# pixracer_sd_usb_can_i2c.net
KiCad netlist of a schematic drawn in Altium Designer
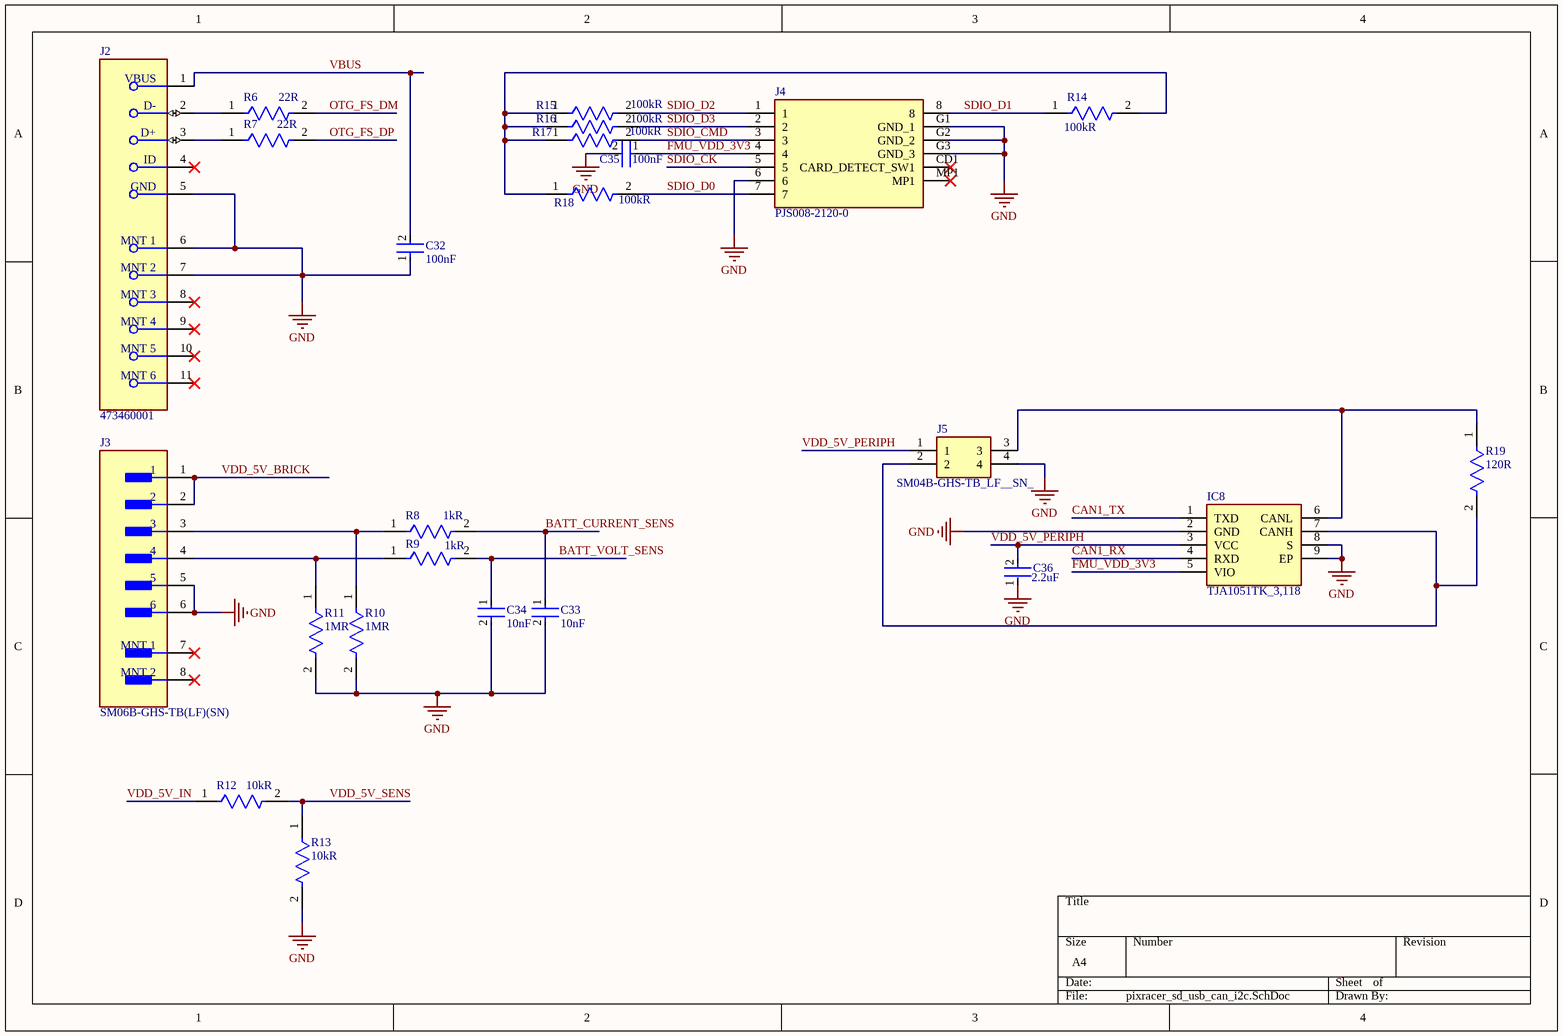
[diagram p0: pixracer_sd_usb_can_i2c.SchDoc]

(export (version "E")
  (design (tool "Eeschema 10.0.6"))
  (components
    (comp (ref "C32")
      (value "0603ZC104MAT2A")
      (footprint "FP-0603-L_1_6_0_15-W_0_81-IPC_B")
      (description "General Purpose Ceramic Capacitor, 0603, 100nF, 20%, X7R, 15%, 10V")
      (fields (field (name "TOLERANCE") "20%") (field (name "CAPACITANCE") "100nF"))
      (libsource (lib "Altium Content Vault") (part "02cd4be3c70576c341d710602a673aa"))
    )
    (comp (ref "C33")
      (value "C1608X5R1H103K080AA")
      (footprint "FP-C1608-080-0_1-MFG")
      (description "Multilayer Ceramic Capacitors 10nF ±10% 50V X5R SMD 0603")
      (fields (field (name "TOLERANCE") "10%") (field (name "CAPACITANCE") "10nF"))
      (libsource (lib "Altium Content Vault") (part "236180d848d6139a670b325ea6854c9"))
    )
    (comp (ref "C34")
      (value "C1608X5R1H103K080AA")
      (footprint "FP-C1608-080-0_1-MFG")
      (description "Multilayer Ceramic Capacitors 10nF ±10% 50V X5R SMD 0603")
      (fields (field (name "TOLERANCE") "10%") (field (name "CAPACITANCE") "10nF"))
      (libsource (lib "Altium Content Vault") (part "236180d848d6139a670b325ea6854c9"))
    )
    (comp (ref "C35")
      (value "0603ZC104MAT2A")
      (footprint "FP-0603-L_1_6_0_15-W_0_81-IPC_B")
      (description "General Purpose Ceramic Capacitor, 0603, 100nF, 20%, X7R, 15%, 10V")
      (fields (field (name "TOLERANCE") "20%") (field (name "CAPACITANCE") "100nF"))
      (libsource (lib "Altium Content Vault") (part "02cd4be3c70576c341d710602a673aa"))
    )
    (comp (ref "C36")
      (value "C1608X7R1A225K080AC")
      (footprint "FP-C1608-080-0_1-MFG")
      (description "Multilayer Ceramic Capacitors 2.2μF ±10% 10V X7R SMD 0603")
      (fields (field (name "CAPACITANCE") "2.2uF") (field (name "TOLERANCE") "10%"))
      (libsource (lib "Altium Content Vault") (part "236180d848d6139a670b325ea6854c9"))
    )
    (comp (ref "IC8")
      (value "TJA1051TK_3,118")
      (footprint "SamacSys:SON65P300X300X100-9N-D")
      (description "Integrated Circuit")
      (fields
        (field (name "MANUFACTURER_PART_NUMBER") "TJA1051TK/3,118")
        (field (name "MOUSER PART NUMBER") "771-TJA1051TK/3118")
      )
      (libsource (lib "*") (part "TJA1051TK_3,118"))
    )
    (comp (ref "J2")
      (value "473460001")
      (footprint "FP-473460001-MFG")
      (description "CONN RCPT USB2.0 MICRO B SMD R/A")
      (fields
        (field (name "OCTOPART") "https://octopart.com/47346-0001-molex-7164928")
        (field (name "MANUFACTURER") "Molex")
      )
      (libsource (lib "Altium Content Vault") (part "53ae1f1d9b557310b43ca686e5bb76a"))
    )
    (comp (ref "J3")
      (value "SM06B-GHS-TB(LF)(SN)")
      (footprint "FP-SM06B-GHS-TB_LF_SN-MFG")
      (description "CONN HEADER SMD R/A 6POS 1.25MM")
      (libsource (lib "Altium Content Vault") (part "ed24c53d9ba001d1a2a686240a95171"))
    )
    (comp (ref "J4")
      (value "PJS008-2120-0")
      (footprint "SamacSys:PJS00821200")
      (description "Connector")
      (fields (field (name "MOUSER PART NUMBER") "945-PJS008-2120-0"))
      (libsource (lib "*") (part "PJS008-2120-0"))
    )
    (comp (ref "J5")
      (value "SM04B-GHS-TB_LF__SN_")
      (footprint "SamacSys:SM04B-GHS-TB")
      (description "Connector")
      (fields (field (name "MANUFACTURER_PART_NUMBER") "SM04B-GHS-TB(LF)(SN)"))
      (libsource (lib "*") (part "SM04B-GHS-TB_LF__SN_"))
    )
    (comp (ref "R6")
      (value "CRCW060322R0JNEAHP")
      (footprint "FP-CRCW0603-HPe3-IPC_A")
      (description "RES Thick Film, 22Ω, 5%, 0.33W, 200ppm/°C, 0603")
      (fields (field (name "TOLERANCE") "5%") (field (name "RESISTANCE") "22R"))
      (libsource (lib "Altium Content Vault") (part "1029c3af85768c4190bb7ad29bc67b5"))
    )
    (comp (ref "R7")
      (value "CRCW060322R0JNEAHP")
      (footprint "FP-CRCW0603-HPe3-IPC_A")
      (description "RES Thick Film, 22Ω, 5%, 0.33W, 200ppm/°C, 0603")
      (fields (field (name "TOLERANCE") "5%") (field (name "RESISTANCE") "22R"))
      (libsource (lib "Altium Content Vault") (part "1029c3af85768c4190bb7ad29bc67b5"))
    )
    (comp (ref "R8")
      (value "RC1608J102CS")
      (footprint "FP-RC1608-IPC_A")
      (description "Res Thick Film 0603 1kΩ 5% 0.1W ±100ppm/°C Molded SMD T/R")
      (fields (field (name "RESISTANCE") "1kR") (field (name "TOLERANCE") "5%"))
      (libsource (lib "Altium Content Vault") (part "1029c3af85768c4190bb7ad29bc67b5"))
    )
    (comp (ref "R9")
      (value "RC1608J102CS")
      (footprint "FP-RC1608-IPC_A")
      (description "Res Thick Film 0603 1kΩ 5% 0.1W ±100ppm/°C Molded SMD T/R")
      (fields (field (name "RESISTANCE") "1kR") (field (name "TOLERANCE") "5%"))
      (libsource (lib "Altium Content Vault") (part "1029c3af85768c4190bb7ad29bc67b5"))
    )
    (comp (ref "R10")
      (value "CRCW06031M00JNEAHP")
      (footprint "FP-CRCW0603-HPe3-IPC_A")
      (description "RES Thick Film, 1MΩ, 5%, 0.33W, 200ppm/°C, 0603")
      (fields (field (name "TOLERANCE") "5%") (field (name "RESISTANCE") "1MR"))
      (libsource (lib "Altium Content Vault") (part "1029c3af85768c4190bb7ad29bc67b5"))
    )
    (comp (ref "R11")
      (value "CRCW06031M00JNEAHP")
      (footprint "FP-CRCW0603-HPe3-IPC_A")
      (description "RES Thick Film, 1MΩ, 5%, 0.33W, 200ppm/°C, 0603")
      (fields (field (name "TOLERANCE") "5%") (field (name "RESISTANCE") "1MR"))
      (libsource (lib "Altium Content Vault") (part "1029c3af85768c4190bb7ad29bc67b5"))
    )
    (comp (ref "R12")
      (value "ERJ-3GEYJ103V")
      (footprint "FP-ERJ3G-IPC_C")
      (description "RES SMD 10K OHM 5% 1/10W 0603")
      (fields (field (name "TOLERANCE") "5%") (field (name "RESISTANCE") "10kR"))
      (libsource (lib "Altium Content Vault") (part "1029c3af85768c4190bb7ad29bc67b5"))
    )
    (comp (ref "R13")
      (value "ERJ-3GEYJ103V")
      (footprint "FP-ERJ3G-IPC_C")
      (description "RES SMD 10K OHM 5% 1/10W 0603")
      (fields (field (name "TOLERANCE") "5%") (field (name "RESISTANCE") "10kR"))
      (libsource (lib "Altium Content Vault") (part "1029c3af85768c4190bb7ad29bc67b5"))
    )
    (comp (ref "R14")
      (value "RMCF0603JT100K")
      (footprint "FP-RMCF0603-IPC_C")
      (description "100kΩ ±5% 0.1W 0603 Thick Film Chip Resistor AEC-Q200 compliant")
      (fields (field (name "RESISTANCE") "100kR") (field (name "TOLERANCE") "5%"))
      (libsource (lib "Altium Content Vault") (part "1029c3af85768c4190bb7ad29bc67b5"))
    )
    (comp (ref "R15")
      (value "RMCF0603JT100K")
      (footprint "FP-RMCF0603-IPC_C")
      (description "100kΩ ±5% 0.1W 0603 Thick Film Chip Resistor AEC-Q200 compliant")
      (fields (field (name "RESISTANCE") "100kR") (field (name "TOLERANCE") "5%"))
      (libsource (lib "Altium Content Vault") (part "1029c3af85768c4190bb7ad29bc67b5"))
    )
    (comp (ref "R16")
      (value "RMCF0603JT100K")
      (footprint "FP-RMCF0603-IPC_C")
      (description "100kΩ ±5% 0.1W 0603 Thick Film Chip Resistor AEC-Q200 compliant")
      (fields (field (name "RESISTANCE") "100kR") (field (name "TOLERANCE") "5%"))
      (libsource (lib "Altium Content Vault") (part "1029c3af85768c4190bb7ad29bc67b5"))
    )
    (comp (ref "R17")
      (value "RMCF0603JT100K")
      (footprint "FP-RMCF0603-IPC_C")
      (description "100kΩ ±5% 0.1W 0603 Thick Film Chip Resistor AEC-Q200 compliant")
      (fields (field (name "RESISTANCE") "100kR") (field (name "TOLERANCE") "5%"))
      (libsource (lib "Altium Content Vault") (part "1029c3af85768c4190bb7ad29bc67b5"))
    )
    (comp (ref "R18")
      (value "RMCF0603JT100K")
      (footprint "FP-RMCF0603-IPC_C")
      (description "100kΩ ±5% 0.1W 0603 Thick Film Chip Resistor AEC-Q200 compliant")
      (fields (field (name "RESISTANCE") "100kR") (field (name "TOLERANCE") "5%"))
      (libsource (lib "Altium Content Vault") (part "1029c3af85768c4190bb7ad29bc67b5"))
    )
    (comp (ref "R19")
      (value "MCT06030D1200BP100")
      (footprint "FP-MCT0603-MFG")
      (description "RES SMD 100 OHM 1% 1/8W 0603")
      (fields (field (name "RESISTANCE") "120R") (field (name "TOLERANCE") "0.1%"))
      (libsource (lib "Altium Content Vault") (part "1029c3af85768c4190bb7ad29bc67b5"))
    )
  )
  (nets
    (net (code "1") (name "/BATT_CURRENT_SENS") (class "Default")
      (node (ref "C33") (pin "1") (pinfunction "1_1") (pintype "passive"))
      (node (ref "R8") (pin "2") (pinfunction "2_2") (pintype "passive"))
    )
    (net (code "2") (name "/BATT_VOLT_SENS") (class "Default")
      (node (ref "C34") (pin "1") (pinfunction "1_1") (pintype "passive"))
      (node (ref "R9") (pin "2") (pinfunction "2_2") (pintype "passive"))
    )
    (net (code "3") (name "/CAN1_RX") (class "Default")
      (node (ref "IC8") (pin "4") (pinfunction "RXD_4") (pintype "passive"))
    )
    (net (code "4") (name "/CAN1_TX") (class "Default")
      (node (ref "IC8") (pin "1") (pinfunction "TXD_1") (pintype "passive"))
    )
    (net (code "5") (name "/FMU_VDD_3V3") (class "Default")
      (node (ref "C35") (pin "1") (pinfunction "1_1") (pintype "passive"))
      (node (ref "IC8") (pin "5") (pinfunction "VIO_5") (pintype "passive"))
      (node (ref "J4") (pin "4") (pinfunction "4_4") (pintype "passive"))
    )
    (net (code "6") (name "/OTG_FS_DM") (class "Default")
      (node (ref "R6") (pin "2") (pinfunction "2_2") (pintype "passive"))
    )
    (net (code "7") (name "/OTG_FS_DP") (class "Default")
      (node (ref "R7") (pin "2") (pinfunction "2_2") (pintype "passive"))
    )
    (net (code "8") (name "/SDIO_CK") (class "Default")
      (node (ref "J4") (pin "5") (pinfunction "5_5") (pintype "passive"))
    )
    (net (code "9") (name "/SDIO_CMD") (class "Default")
      (node (ref "J4") (pin "3") (pinfunction "3_3") (pintype "passive"))
      (node (ref "R17") (pin "2") (pinfunction "2_2") (pintype "passive"))
    )
    (net (code "10") (name "/SDIO_D0") (class "Default")
      (node (ref "J4") (pin "7") (pinfunction "7_7") (pintype "passive"))
      (node (ref "R18") (pin "2") (pinfunction "2_2") (pintype "passive"))
    )
    (net (code "11") (name "/SDIO_D1") (class "Default")
      (node (ref "J4") (pin "8") (pinfunction "8_8") (pintype "passive"))
      (node (ref "R14") (pin "1") (pinfunction "1_1") (pintype "passive"))
    )
    (net (code "12") (name "/SDIO_D2") (class "Default")
      (node (ref "J4") (pin "1") (pinfunction "1_1") (pintype "passive"))
      (node (ref "R15") (pin "2") (pinfunction "2_2") (pintype "passive"))
    )
    (net (code "13") (name "/SDIO_D3") (class "Default")
      (node (ref "J4") (pin "2") (pinfunction "2_2") (pintype "passive"))
      (node (ref "R16") (pin "2") (pinfunction "2_2") (pintype "passive"))
    )
    (net (code "14") (name "/VBUS") (class "Default")
      (node (ref "C32") (pin "2") (pinfunction "2_2") (pintype "passive"))
      (node (ref "J2") (pin "1") (pinfunction "VBUS_1") (pintype "power_in"))
    )
    (net (code "15") (name "/VDD_5V_BRICK") (class "Default")
      (node (ref "J3") (pin "1") (pinfunction "1_1") (pintype "passive"))
      (node (ref "J3") (pin "2") (pinfunction "2_2") (pintype "passive"))
    )
    (net (code "16") (name "/VDD_5V_IN") (class "Default")
      (node (ref "R12") (pin "1") (pinfunction "1_1") (pintype "passive"))
    )
    (net (code "17") (name "/VDD_5V_PERIPH") (class "Default")
      (node (ref "C36") (pin "2") (pinfunction "2_2") (pintype "passive"))
      (node (ref "IC8") (pin "3") (pinfunction "VCC_3") (pintype "passive"))
      (node (ref "J5") (pin "1") (pinfunction "1_1") (pintype "passive"))
    )
    (net (code "18") (name "/VDD_5V_SENS") (class "Default")
      (node (ref "R12") (pin "2") (pinfunction "2_2") (pintype "passive"))
      (node (ref "R13") (pin "1") (pinfunction "1_1") (pintype "passive"))
    )
    (net (code "19") (name "GND") (class "Default")
      (node (ref "C32") (pin "1") (pinfunction "1_1") (pintype "passive"))
      (node (ref "C33") (pin "2") (pinfunction "2_2") (pintype "passive"))
      (node (ref "C34") (pin "2") (pinfunction "2_2") (pintype "passive"))
      (node (ref "C35") (pin "2") (pinfunction "2_2") (pintype "passive"))
      (node (ref "C36") (pin "1") (pinfunction "1_1") (pintype "passive"))
      (node (ref "IC8") (pin "2") (pinfunction "GND_2") (pintype "passive"))
      (node (ref "IC8") (pin "8") (pinfunction "S_8") (pintype "passive"))
      (node (ref "IC8") (pin "9") (pinfunction "EP_9") (pintype "passive"))
      (node (ref "J2") (pin "5") (pinfunction "GND_5") (pintype "power_in"))
      (node (ref "J2") (pin "6") (pinfunction "MNT_1_6") (pintype "passive"))
      (node (ref "J2") (pin "7") (pinfunction "MNT_2_7") (pintype "passive"))
      (node (ref "J3") (pin "5") (pinfunction "5_5") (pintype "passive"))
      (node (ref "J3") (pin "6") (pinfunction "6_6") (pintype "passive"))
      (node (ref "J4") (pin "6") (pinfunction "6_6") (pintype "passive"))
      (node (ref "J4") (pin "G1") (pinfunction "GND_1_G1") (pintype "passive"))
      (node (ref "J4") (pin "G2") (pinfunction "GND_2_G2") (pintype "passive"))
      (node (ref "J4") (pin "G3") (pinfunction "GND_3_G3") (pintype "passive"))
      (node (ref "J5") (pin "4") (pinfunction "4_4") (pintype "passive"))
      (node (ref "R10") (pin "2") (pinfunction "2_2") (pintype "passive"))
      (node (ref "R11") (pin "2") (pinfunction "2_2") (pintype "passive"))
      (node (ref "R13") (pin "2") (pinfunction "2_2") (pintype "passive"))
    )
    (net (code "20") (name "Net-(IC8-CANH)") (class "Default")
      (node (ref "IC8") (pin "7") (pinfunction "CANH_7") (pintype "passive"))
      (node (ref "J5") (pin "2") (pinfunction "2_2") (pintype "passive"))
      (node (ref "R19") (pin "2") (pinfunction "2_2") (pintype "passive"))
    )
    (net (code "21") (name "Net-(IC8-CANL)") (class "Default")
      (node (ref "IC8") (pin "6") (pinfunction "CANL_6") (pintype "passive"))
      (node (ref "J5") (pin "3") (pinfunction "3_3") (pintype "passive"))
      (node (ref "R19") (pin "1") (pinfunction "1_1") (pintype "passive"))
    )
    (net (code "22") (name "Net-(J2-D+)") (class "Default")
      (node (ref "J2") (pin "3") (pinfunction "D+_3") (pintype "bidirectional"))
      (node (ref "R7") (pin "1") (pinfunction "1_1") (pintype "passive"))
    )
    (net (code "23") (name "Net-(J2-D-)") (class "Default")
      (node (ref "J2") (pin "2") (pinfunction "D-_2") (pintype "bidirectional"))
      (node (ref "R6") (pin "1") (pinfunction "1_1") (pintype "passive"))
    )
    (net (code "24") (name "Net-(J3-Pad3)") (class "Default")
      (node (ref "J3") (pin "3") (pinfunction "3_3") (pintype "passive"))
      (node (ref "R10") (pin "1") (pinfunction "1_1") (pintype "passive"))
      (node (ref "R8") (pin "1") (pinfunction "1_1") (pintype "passive"))
    )
    (net (code "25") (name "Net-(J3-Pad4)") (class "Default")
      (node (ref "J3") (pin "4") (pinfunction "4_4") (pintype "passive"))
      (node (ref "R11") (pin "1") (pinfunction "1_1") (pintype "passive"))
      (node (ref "R9") (pin "1") (pinfunction "1_1") (pintype "passive"))
    )
    (net (code "26") (name "Net-(R14-Pad2)") (class "Default")
      (node (ref "R14") (pin "2") (pinfunction "2_2") (pintype "passive"))
      (node (ref "R15") (pin "1") (pinfunction "1_1") (pintype "passive"))
      (node (ref "R16") (pin "1") (pinfunction "1_1") (pintype "passive"))
      (node (ref "R17") (pin "1") (pinfunction "1_1") (pintype "passive"))
      (node (ref "R18") (pin "1") (pinfunction "1_1") (pintype "passive"))
    )
    (net (code "27") (name "unconnected-(J2-ID-Pad4)") (class "Default")
      (node (ref "J2") (pin "4") (pinfunction "ID_4") (pintype "passive+no_connect"))
    )
    (net (code "28") (name "unconnected-(J2-MNT_3-Pad8)") (class "Default")
      (node (ref "J2") (pin "8") (pinfunction "MNT_3_8") (pintype "passive+no_connect"))
    )
    (net (code "29") (name "unconnected-(J2-MNT_4-Pad9)") (class "Default")
      (node (ref "J2") (pin "9") (pinfunction "MNT_4_9") (pintype "passive+no_connect"))
    )
    (net (code "30") (name "unconnected-(J2-MNT_5-Pad10)") (class "Default")
      (node (ref "J2") (pin "10") (pinfunction "MNT_5_10") (pintype "passive+no_connect"))
    )
    (net (code "31") (name "unconnected-(J2-MNT_6-Pad11)") (class "Default")
      (node (ref "J2") (pin "11") (pinfunction "MNT_6_11") (pintype "passive+no_connect"))
    )
    (net (code "32") (name "unconnected-(J3-MNT_1-Pad7)") (class "Default")
      (node (ref "J3") (pin "7") (pinfunction "MNT_1_7") (pintype "passive+no_connect"))
    )
    (net (code "33") (name "unconnected-(J3-MNT_2-Pad8)") (class "Default")
      (node (ref "J3") (pin "8") (pinfunction "MNT_2_8") (pintype "passive+no_connect"))
    )
    (net (code "34") (name "unconnected-(J4-CARD_DETECT_SW1-PadCD1)") (class "Default")
      (node (ref "J4") (pin "CD1") (pinfunction "CARD_DETECT_SW1_CD1") (pintype "passive+no_connect"))
    )
    (net (code "35") (name "unconnected-(J4-PadMP1)") (class "Default")
      (node (ref "J4") (pin "MP1") (pinfunction "MP1_MP1") (pintype "passive+no_connect"))
    )
  )
)
